# tampinha.net
KiCad netlist of a schematic drawn in EAGLE
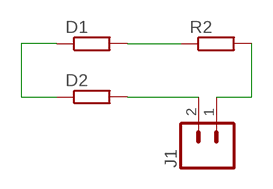
[diagram p0: schematic, sheet 1]

(export (version "E")
  (design (tool "Eeschema 10.0.6"))
  (components
    (comp (ref "D1")
      (value "R-EU_0204/7")
      (footprint "eagle-import:0204_7")
      (libsource (lib "eagle-import") (part "R-EU_0204/7"))
    )
    (comp (ref "D2")
      (value "R-EU_0204/7")
      (footprint "eagle-import:0204_7")
      (libsource (lib "eagle-import") (part "R-EU_0204/7"))
    )
    (comp (ref "J1")
      (value "CONN_02")
      (footprint "eagle-import:1X02")
      (libsource (lib "eagle-import") (part "CONN_02"))
    )
    (comp (ref "R2")
      (value "R-EU_0204/7")
      (footprint "eagle-import:0204_7")
      (libsource (lib "eagle-import") (part "R-EU_0204/7"))
    )
  )
  (nets
    (net (code "1") (name "Net-(D1-Pad1)") (class "Default")
      (node (ref "D1") (pin "1") (pinfunction "1_1") (pintype "passive"))
      (node (ref "D2") (pin "1") (pinfunction "1_1") (pintype "passive"))
    )
    (net (code "2") (name "Net-(D1-Pad2)") (class "Default")
      (node (ref "D1") (pin "2") (pinfunction "2_2") (pintype "passive"))
      (node (ref "R2") (pin "1") (pinfunction "1_1") (pintype "passive"))
    )
    (net (code "3") (name "Net-(D2-Pad2)") (class "Default")
      (node (ref "D2") (pin "2") (pinfunction "2_2") (pintype "passive"))
      (node (ref "J1") (pin "2") (pinfunction "2_2") (pintype "passive"))
    )
    (net (code "4") (name "Net-(J1-Pad1)") (class "Default")
      (node (ref "J1") (pin "1") (pinfunction "1_1") (pintype "passive"))
      (node (ref "R2") (pin "2") (pinfunction "2_2") (pintype "passive"))
    )
  )
)
